# CH32V205V-R0.net
KiCad netlist of a schematic drawn in Altium Designer
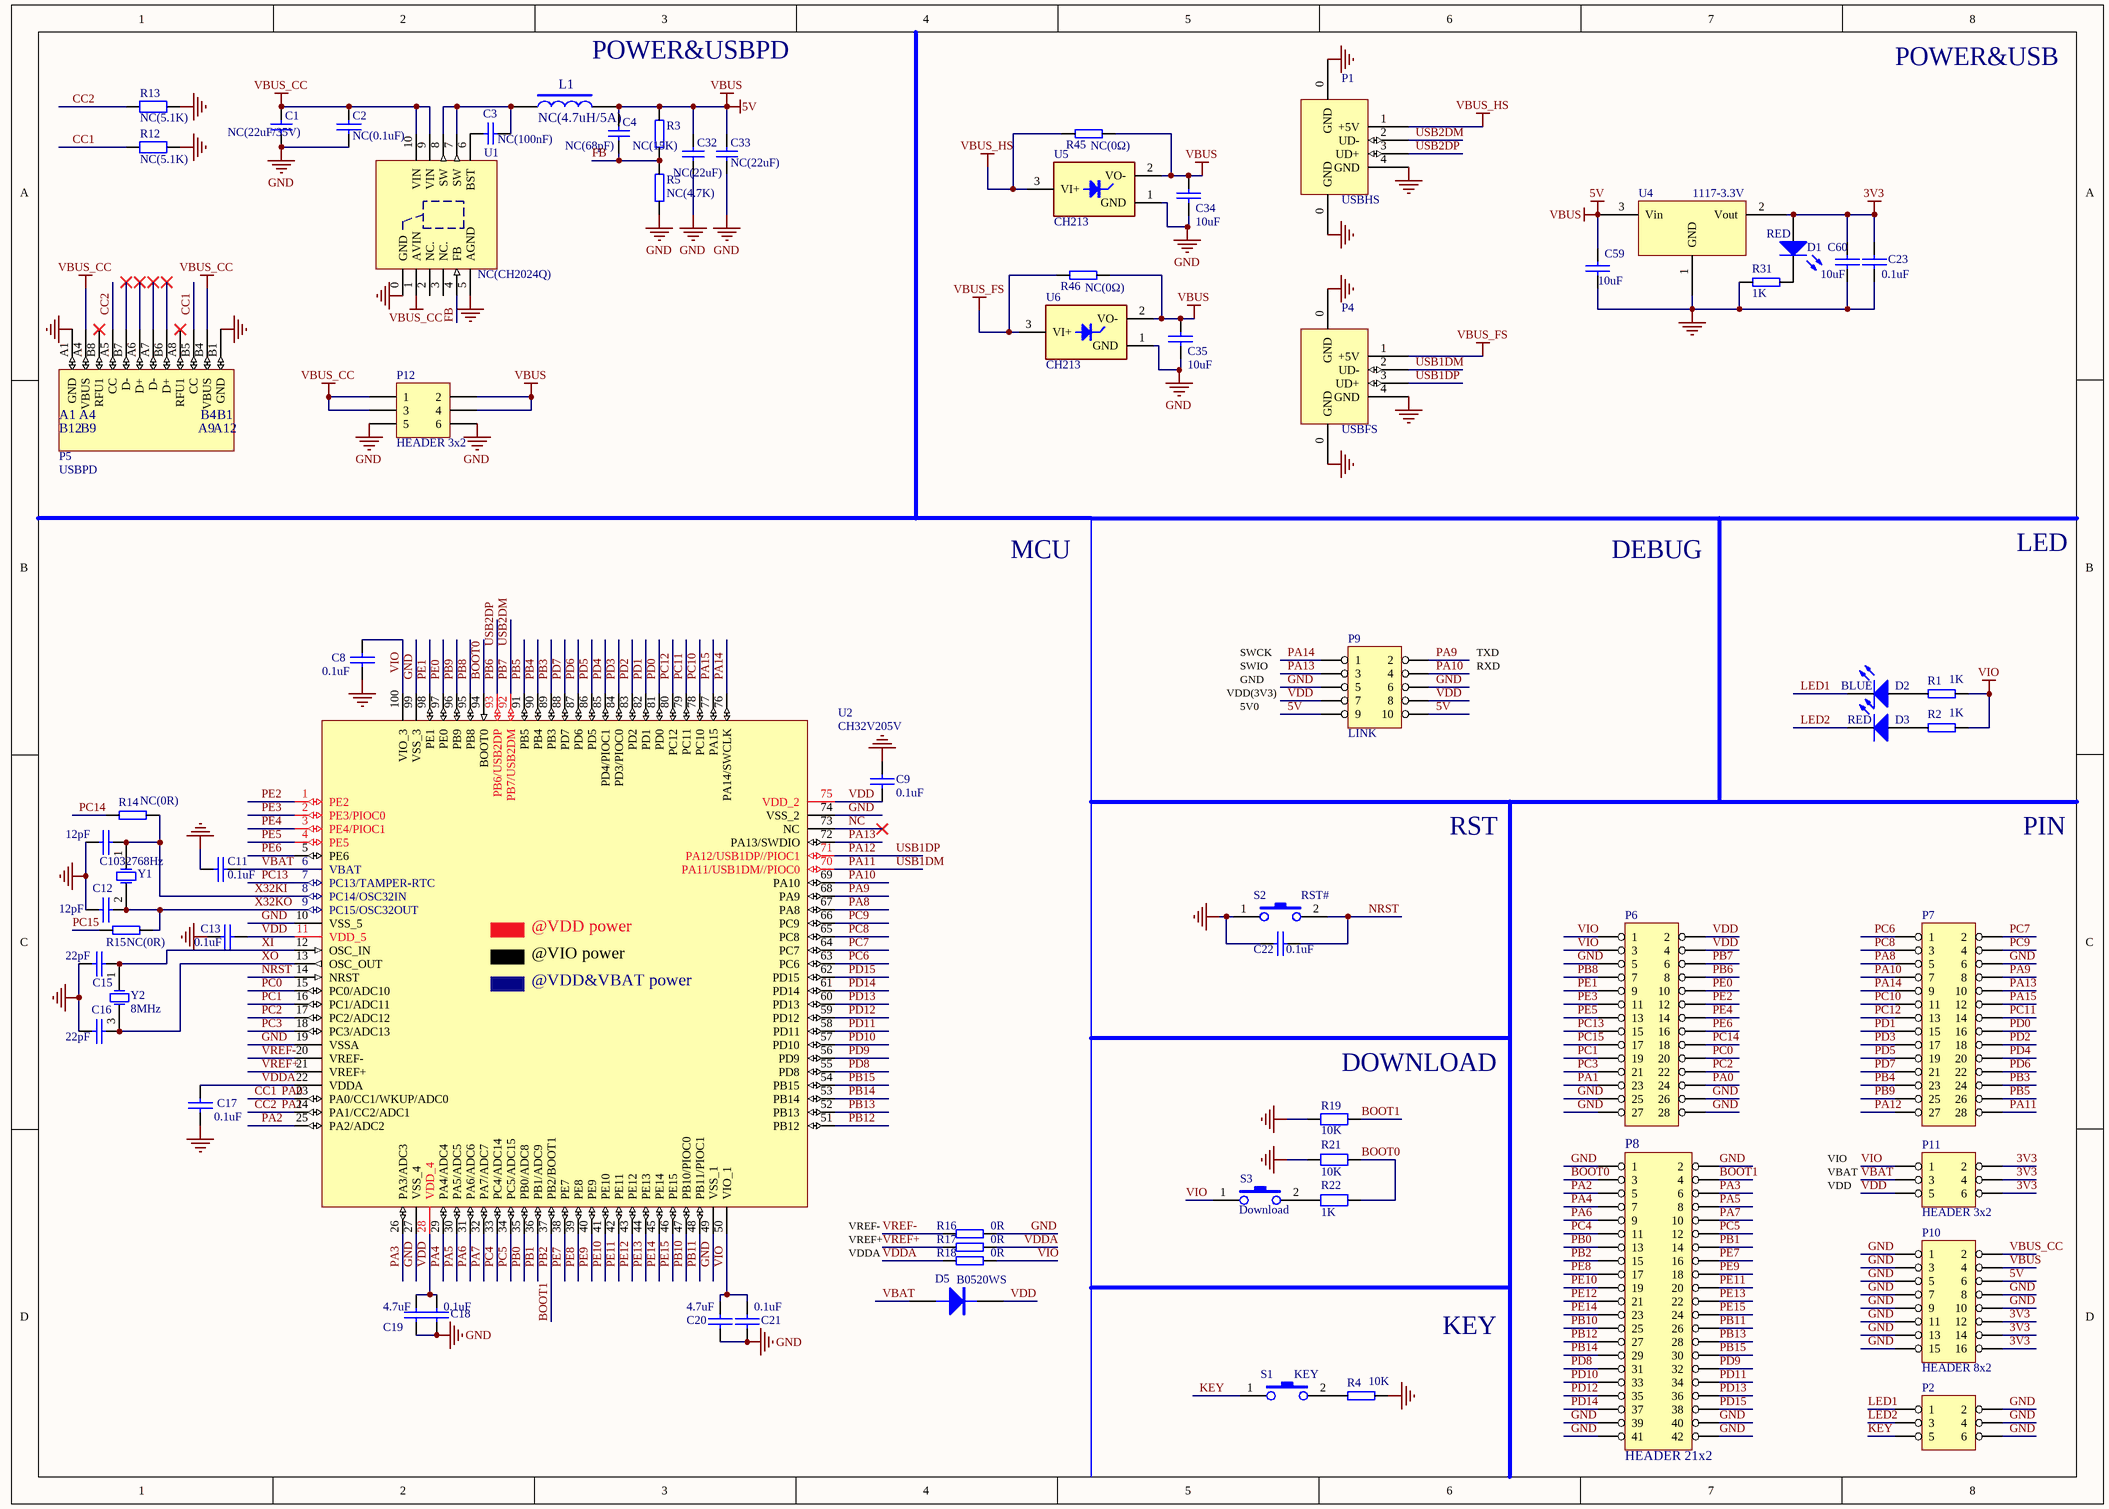
[diagram p0: CH32V205V-R0.SchDoc]

(export (version "E")
  (design (tool "Eeschema 10.0.6"))
  (components
    (comp (ref "C1")
      (value "NC(22uF/35V)")
      (footprint "0805_C")
      (description "贴片电容")
      (libsource (lib "Miscellaneous Devices LC") (part "0603 100nF (104) 10% 50V"))
    )
    (comp (ref "C2")
      (value "NC(0.1uF)")
      (footprint "0402_C")
      (description "Capacitor")
      (libsource (lib "*") (part "CAP"))
    )
    (comp (ref "C3")
      (value "NC(100nF)")
      (footprint "0402_C")
      (description "贴片电容")
      (libsource (lib "Miscellaneous Devices LC") (part "0603 1uF (105) 10% 50V"))
    )
    (comp (ref "C4")
      (value "NC(68pF)")
      (footprint "0402_C")
      (description "贴片电容")
      (libsource (lib "Miscellaneous Devices LC") (part "0603 100nF (104) 10% 50V"))
    )
    (comp (ref "C8")
      (value "0.1uF")
      (footprint "0402_C")
      (description "Capacitor")
      (libsource (lib "*") (part "CAP"))
    )
    (comp (ref "C9")
      (value "0.1uF")
      (footprint "0402_C")
      (description "Capacitor")
      (libsource (lib "*") (part "CAP"))
    )
    (comp (ref "C10")
      (value "12pF")
      (footprint "0402_C")
      (description "Capacitor")
      (libsource (lib "*") (part "CAP"))
    )
    (comp (ref "C11")
      (value "0.1uF")
      (footprint "0402_C")
      (description "Capacitor")
      (libsource (lib "*") (part "CAP"))
    )
    (comp (ref "C12")
      (value "12pF")
      (footprint "0402_C")
      (description "Capacitor")
      (libsource (lib "*") (part "CAP"))
    )
    (comp (ref "C13")
      (value "0.1uF")
      (footprint "0402_C")
      (description "Capacitor")
      (libsource (lib "*") (part "CAP"))
    )
    (comp (ref "C15")
      (value "22pF")
      (footprint "0402_C")
      (description "Capacitor")
      (libsource (lib "*") (part "CAP"))
    )
    (comp (ref "C16")
      (value "22pF")
      (footprint "0402_C")
      (description "Capacitor")
      (libsource (lib "*") (part "CAP"))
    )
    (comp (ref "C17")
      (value "0.1uF")
      (footprint "0402_C")
      (description "Capacitor")
      (libsource (lib "*") (part "CAP"))
    )
    (comp (ref "C18")
      (value "0.1uF")
      (footprint "0402_C")
      (description "Capacitor")
      (libsource (lib "*") (part "CAP"))
    )
    (comp (ref "C19")
      (value "4.7uF")
      (footprint "0402_C")
      (description "Capacitor")
      (libsource (lib "*") (part "CAP"))
    )
    (comp (ref "C20")
      (value "4.7uF")
      (footprint "0402_C")
      (description "Capacitor")
      (libsource (lib "*") (part "CAP"))
    )
    (comp (ref "C21")
      (value "0.1uF")
      (footprint "0402_C")
      (description "Capacitor")
      (libsource (lib "*") (part "CAP"))
    )
    (comp (ref "C22")
      (value "0.1uF")
      (footprint "0402_C")
      (description "Capacitor")
      (libsource (lib "") (part "CAP_1"))
    )
    (comp (ref "C23")
      (value "0.1uF")
      (footprint "0402_C")
      (description "Capacitor")
      (libsource (lib "*") (part "CAP"))
    )
    (comp (ref "C32")
      (value "NC(22uF)")
      (footprint "0805_C")
      (description "贴片电容")
      (libsource (lib "Miscellaneous Devices LC") (part "0603 100nF (104) 10% 50V"))
    )
    (comp (ref "C33")
      (value "NC(22uF)")
      (footprint "0805_C")
      (description "贴片电容")
      (libsource (lib "Miscellaneous Devices LC") (part "0603 100nF (104) 10% 50V"))
    )
    (comp (ref "C34")
      (value "10uF")
      (footprint "0603_C")
      (description "Capacitor")
      (libsource (lib "") (part "CAP_1"))
    )
    (comp (ref "C35")
      (value "10uF")
      (footprint "0603_C")
      (description "Capacitor")
      (libsource (lib "") (part "CAP_1"))
    )
    (comp (ref "C59")
      (value "10uF")
      (footprint "0603_C")
      (description "Capacitor")
      (libsource (lib "*") (part "CAP"))
    )
    (comp (ref "C60")
      (value "10uF")
      (footprint "0603_C")
      (description "Capacitor")
      (libsource (lib "*") (part "CAP"))
    )
    (comp (ref "D1")
      (value "RED")
      (footprint "0603+")
      (description "Typical INFRARED GaAs LED")
      (fields (field (name "PUBLISHER") "Altium Limited"))
      (libsource (lib "*") (part "LED0"))
    )
    (comp (ref "D2")
      (value "BLUE")
      (footprint "0603+")
      (description "Typical INFRARED GaAs LED")
      (fields (field (name "PUBLISHER") "Altium Limited"))
      (libsource (lib "*") (part "LED0"))
    )
    (comp (ref "D3")
      (value "RED")
      (footprint "0603+")
      (description "Typical INFRARED GaAs LED")
      (fields (field (name "PUBLISHER") "Altium Limited"))
      (libsource (lib "*") (part "LED0"))
    )
    (comp (ref "D5")
      (value "B0520WS")
      (footprint "SOD-323")
      (description "Diode")
      (libsource (lib "*") (part "DIODE"))
    )
    (comp (ref "L1")
      (value "NC(4.7uH/5A)")
      (footprint "IND-SMD_L7.0-W6.6")
      (libsource (lib "wch_sch_others") (part "INDUCTOR"))
    )
    (comp (ref "P1")
      (value "USBHS")
      (footprint "USBAF")
      (description "USB Port")
      (libsource (lib "*") (part "USB"))
    )
    (comp (ref "P2")
      (value "IO")
      (footprint "MYPCB:IDC6-2.54mm")
      (description "Header, 3-Pin, Dual row")
      (libsource (lib "wch_sch_others") (part "HEADER 3x2"))
    )
    (comp (ref "P4")
      (value "USBFS")
      (footprint "USBAF")
      (description "USB Port")
      (libsource (lib "*") (part "USB"))
    )
    (comp (ref "P5")
      (value "USBPD")
      (footprint "TYPE-C-Receptacle-2.0")
      (libsource (lib "*") (part "TYPE-C1"))
    )
    (comp (ref "P6")
      (value "~")
      (footprint "MYPCB:IDC28-2.54MM")
      (description "Header, 14-Pin, Dual row")
      (libsource (lib "wch_sch_others") (part "HEADER 14x2"))
    )
    (comp (ref "P7")
      (value "~")
      (footprint "MYPCB:IDC28-2.54MM")
      (description "Header, 14-Pin, Dual row")
      (libsource (lib "wch_sch_others") (part "HEADER 14x2"))
    )
    (comp (ref "P8")
      (value "HEADER 21x2")
      (footprint "MYPCB:IDC42-2.54MM")
      (description "Header, 21-Pin, Dual row")
      (libsource (lib "wch_sch_others") (part "HEADER 21x2"))
    )
    (comp (ref "P9")
      (value "LINK")
      (footprint "MYPCB:IDC10-2.54mm")
      (description "Header, 5-Pin, Dual row")
      (libsource (lib "wch_sch_others") (part "HEADER 5x2"))
    )
    (comp (ref "P10")
      (value "HEADER 8x2")
      (footprint "MYPCB:IDC16-2.54mm")
      (description "Header, 8-Pin, Dual row")
      (libsource (lib "wch_sch_others") (part "HEADER 8x2"))
    )
    (comp (ref "P11")
      (value "HEADER 3x2")
      (footprint "MYPCB:IDC6-2.54mm")
      (description "Header, 3-Pin, Dual row")
      (libsource (lib "wch_sch_others") (part "HEADER 3x2"))
    )
    (comp (ref "P12")
      (value "HEADER 3x2")
      (footprint "MYPCB:IDC6-2.54mm")
      (description "Header, 3-Pin, Dual row")
      (libsource (lib "") (part "HEADER 3x2_1"))
    )
    (comp (ref "R1") (value "1K") (footprint "0402") (libsource (lib "wch_sch_others") (part "RES")))
    (comp (ref "R2") (value "1K") (footprint "0402") (libsource (lib "wch_sch_others") (part "RES")))
    (comp (ref "R3") (value "NC(15K)") (footprint "0402") (libsource (lib "wch_sch_others(1)") (part "RES")))
    (comp (ref "R4") (value "10K") (footprint "0402") (libsource (lib "wch_sch_others") (part "RES")))
    (comp (ref "R5") (value "NC(4.7K)") (footprint "0402") (libsource (lib "wch_sch_others(1)") (part "RES")))
    (comp (ref "R12")
      (value "NC(5.1K)")
      (footprint "0402")
      (description "Resistor")
      (libsource (lib "") (part "Res2_1"))
    )
    (comp (ref "R13")
      (value "NC(5.1K)")
      (footprint "0402")
      (description "Resistor")
      (libsource (lib "") (part "Res2_1"))
    )
    (comp (ref "R14") (value "NC(0R)") (footprint "0402") (libsource (lib "wch_sch_others") (part "RES")))
    (comp (ref "R15") (value "NC(0R)") (footprint "0402") (libsource (lib "wch_sch_others") (part "RES")))
    (comp (ref "R16") (value "0R") (footprint "0402") (libsource (lib "*") (part "R")))
    (comp (ref "R17") (value "0R") (footprint "0402") (libsource (lib "*") (part "R")))
    (comp (ref "R18") (value "0R") (footprint "0402") (libsource (lib "*") (part "R")))
    (comp (ref "R19")
      (value "10K")
      (footprint "0402")
      (description "Resistor")
      (fields (field (name "PUBLISHER") "Altium Limited"))
      (libsource (lib "Miscellaneous Devices") (part "Res2"))
    )
    (comp (ref "R21")
      (value "10K")
      (footprint "0402")
      (description "Resistor")
      (fields (field (name "PUBLISHER") "Altium Limited"))
      (libsource (lib "Miscellaneous Devices") (part "Res2"))
    )
    (comp (ref "R22")
      (value "1K")
      (footprint "0402")
      (description "Resistor")
      (fields (field (name "PUBLISHER") "Altium Limited"))
      (libsource (lib "Miscellaneous Devices") (part "Res2"))
    )
    (comp (ref "R31") (value "1K") (footprint "0402") (libsource (lib "wch_sch_others") (part "RES")))
    (comp (ref "R45") (value "NC(0Ω)") (footprint "0402") (libsource (lib "wch_sch_others") (part "RES")))
    (comp (ref "R46") (value "NC(0Ω)") (footprint "0402") (libsource (lib "wch_sch_others") (part "RES")))
    (comp (ref "S1")
      (value "KEY")
      (footprint "SMD_6.1x3.65x2.5mm-KEY")
      (libsource (lib "wch_sch_others") (part "KEY1"))
    )
    (comp (ref "S2")
      (value "RST#")
      (footprint "SMD_6.1x3.65x2.5mm-KEY")
      (libsource (lib "wch_sch_others") (part "KEY1"))
    )
    (comp (ref "S3")
      (value "Download")
      (footprint "SMD_6.1x3.65x2.5mm-KEY")
      (libsource (lib "wch_sch_others") (part "KEY1"))
    )
    (comp (ref "U1")
      (value "NC(CH2024Q)")
      (footprint "DFN10_3X3")
      (description "Step-Down DC-DC Converter, 28V input, FB 1.2V, 3A output")
      (libsource (lib "DHXXXSCH") (part "CH2024Q"))
    )
    (comp (ref "U2")
      (value "CH32V205V")
      (footprint "LQFP100")
      (description "RISC-V MCU, 192MHz, USB_480M, USB FS, PD, PIOC, ADC, TKEY, 2*OPA, 2*CMP")
      (libsource (lib "CHXXX") (part "CH32V205V"))
    )
    (comp (ref "U4")
      (value "1117-3.3V")
      (footprint "SOT-223")
      (libsource (lib "wch_sch_others") (part "1117-3.3V"))
    )
    (comp (ref "U5")
      (value "CH213")
      (footprint "SOT-23-3")
      (description "Ideal Diode 5V*1A")
      (libsource (lib "CHXXX") (part "CH213E"))
    )
    (comp (ref "U6")
      (value "CH213")
      (footprint "SOT-23-3")
      (description "Ideal Diode 5V*1A")
      (libsource (lib "CHXXX") (part "CH213E"))
    )
    (comp (ref "Y1")
      (value "32768Hz")
      (footprint "FC-135")
      (description "Crystal Oscillator")
      (fields (field (name "PUBLISHER") "Altium Limited"))
      (libsource (lib "") (part "XTAL_1"))
    )
    (comp (ref "Y2")
      (value "8MHz")
      (footprint "XT3225")
      (description "Crystal Oscillator")
      (fields (field (name "PUBLISHER") "Altium Limited"))
      (libsource (lib "*") (part "XTAL"))
    )
  )
  (nets
    (net (code "2") (name "/BOOT0") (class "Default")
      (node (ref "P8") (pin "3") (pinfunction "3_3") (pintype "passive"))
      (node (ref "R21") (pin "1") (pinfunction "1_1") (pintype "passive"))
      (node (ref "R22") (pin "1") (pinfunction "1_1") (pintype "passive"))
      (node (ref "U2") (pin "94") (pinfunction "BOOT0_94") (pintype "input"))
    )
    (net (code "3") (name "/BOOT1") (class "Default")
      (node (ref "P8") (pin "15") (pinfunction "15_15") (pintype "passive"))
      (node (ref "P8") (pin "4") (pinfunction "4_4") (pintype "passive"))
      (node (ref "R19") (pin "1") (pinfunction "1_1") (pintype "passive"))
      (node (ref "U2") (pin "37") (pinfunction "PB2/BOOT1_37") (pintype "bidirectional"))
    )
    (net (code "4") (name "/CC1") (class "Default")
      (node (ref "P5") (pin "B5") (pinfunction "CC_B5") (pintype "bidirectional"))
      (node (ref "P6") (pin "24") (pinfunction "24_24") (pintype "passive"))
      (node (ref "R12") (pin "1") (pinfunction "1_1") (pintype "passive"))
      (node (ref "U2") (pin "23") (pinfunction "PA0/CC1/WKUP/ADC0_23") (pintype "bidirectional"))
    )
    (net (code "5") (name "/CC2") (class "Default")
      (node (ref "P5") (pin "A5") (pinfunction "CC_A5") (pintype "bidirectional"))
      (node (ref "P6") (pin "23") (pinfunction "23_23") (pintype "passive"))
      (node (ref "R13") (pin "1") (pinfunction "1_1") (pintype "passive"))
      (node (ref "U2") (pin "24") (pinfunction "PA1/CC2/ADC1_24") (pintype "bidirectional"))
    )
    (net (code "6") (name "/FB") (class "Default")
      (node (ref "C4") (pin "2") (pinfunction "2_2") (pintype "passive"))
      (node (ref "R3") (pin "1") (pintype "passive"))
      (node (ref "R5") (pin "2") (pintype "passive"))
      (node (ref "U1") (pin "4") (pinfunction "FB_4") (pintype "input"))
    )
    (net (code "7") (name "/KEY") (class "Default")
      (node (ref "P2") (pin "5") (pinfunction "5_5") (pintype "passive"))
      (node (ref "S1") (pin "1") (pinfunction "1_1") (pintype "passive"))
    )
    (net (code "8") (name "/LED1") (class "Default")
      (node (ref "D2") (pin "2") (pinfunction "K_2") (pintype "passive"))
      (node (ref "P2") (pin "1") (pinfunction "1_1") (pintype "passive"))
    )
    (net (code "9") (name "/LED2") (class "Default")
      (node (ref "D3") (pin "2") (pinfunction "K_2") (pintype "passive"))
      (node (ref "P2") (pin "3") (pinfunction "3_3") (pintype "passive"))
    )
    (net (code "10") (name "/NC") (class "Default")
      (node (ref "U2") (pin "73") (pinfunction "NC_73") (pintype "tri_state+no_connect"))
    )
    (net (code "11") (name "/NRST") (class "Default")
      (node (ref "C22") (pin "2") (pinfunction "2_2") (pintype "passive"))
      (node (ref "S2") (pin "2") (pinfunction "2_2") (pintype "passive"))
      (node (ref "U2") (pin "14") (pinfunction "NRST_14") (pintype "input"))
    )
    (net (code "12") (name "/PA2") (class "Default")
      (node (ref "P8") (pin "5") (pinfunction "5_5") (pintype "passive"))
      (node (ref "U2") (pin "25") (pinfunction "PA2/ADC2_25") (pintype "bidirectional"))
    )
    (net (code "13") (name "/PA3") (class "Default")
      (node (ref "P8") (pin "6") (pinfunction "6_6") (pintype "passive"))
      (node (ref "U2") (pin "26") (pinfunction "PA3/ADC3_26") (pintype "bidirectional"))
    )
    (net (code "14") (name "/PA4") (class "Default")
      (node (ref "P8") (pin "7") (pinfunction "7_7") (pintype "passive"))
      (node (ref "U2") (pin "29") (pinfunction "PA4/ADC4_29") (pintype "bidirectional"))
    )
    (net (code "15") (name "/PA5") (class "Default")
      (node (ref "P8") (pin "8") (pinfunction "8_8") (pintype "passive"))
      (node (ref "U2") (pin "30") (pinfunction "PA5/ADC5_30") (pintype "bidirectional"))
    )
    (net (code "16") (name "/PA6") (class "Default")
      (node (ref "P8") (pin "9") (pinfunction "9_9") (pintype "passive"))
      (node (ref "U2") (pin "31") (pinfunction "PA6/ADC6_31") (pintype "bidirectional"))
    )
    (net (code "17") (name "/PA7") (class "Default")
      (node (ref "P8") (pin "10") (pinfunction "10_10") (pintype "passive"))
      (node (ref "U2") (pin "32") (pinfunction "PA7/ADC7_32") (pintype "bidirectional"))
    )
    (net (code "18") (name "/PA8") (class "Default")
      (node (ref "P7") (pin "5") (pinfunction "5_5") (pintype "passive"))
      (node (ref "U2") (pin "67") (pinfunction "PA8_67") (pintype "bidirectional"))
    )
    (net (code "19") (name "/PA9") (class "Default")
      (node (ref "P7") (pin "8") (pinfunction "8_8") (pintype "passive"))
      (node (ref "P9") (pin "2") (pinfunction "2_2") (pintype "passive"))
      (node (ref "U2") (pin "68") (pinfunction "PA9_68") (pintype "bidirectional"))
    )
    (net (code "20") (name "/PA10") (class "Default")
      (node (ref "P7") (pin "7") (pinfunction "7_7") (pintype "passive"))
      (node (ref "P9") (pin "4") (pinfunction "4_4") (pintype "passive"))
      (node (ref "U2") (pin "69") (pinfunction "PA10_69") (pintype "bidirectional"))
    )
    (net (code "21") (name "/PA11") (class "Default")
      (node (ref "P4") (pin "2") (pinfunction "UD-_2") (pintype "bidirectional"))
      (node (ref "P7") (pin "28") (pinfunction "28_28") (pintype "passive"))
      (node (ref "U2") (pin "70") (pinfunction "PA11/USB1DM//PIOC0_70") (pintype "bidirectional"))
    )
    (net (code "22") (name "/PA12") (class "Default")
      (node (ref "P4") (pin "3") (pinfunction "UD+_3") (pintype "bidirectional"))
      (node (ref "P7") (pin "27") (pinfunction "27_27") (pintype "passive"))
      (node (ref "U2") (pin "71") (pinfunction "PA12/USB1DP//PIOC1_71") (pintype "bidirectional"))
    )
    (net (code "23") (name "/PA13") (class "Default")
      (node (ref "P7") (pin "10") (pinfunction "10_10") (pintype "passive"))
      (node (ref "P9") (pin "3") (pinfunction "3_3") (pintype "passive"))
      (node (ref "U2") (pin "72") (pinfunction "PA13/SWDIO_72") (pintype "bidirectional"))
    )
    (net (code "24") (name "/PA14") (class "Default")
      (node (ref "P7") (pin "9") (pinfunction "9_9") (pintype "passive"))
      (node (ref "P9") (pin "1") (pinfunction "1_1") (pintype "passive"))
      (node (ref "U2") (pin "76") (pinfunction "PA14/SWCLK_76") (pintype "bidirectional"))
    )
    (net (code "25") (name "/PA15") (class "Default")
      (node (ref "P7") (pin "12") (pinfunction "12_12") (pintype "passive"))
      (node (ref "U2") (pin "77") (pinfunction "PA15_77") (pintype "bidirectional"))
    )
    (net (code "26") (name "/PB0") (class "Default")
      (node (ref "P8") (pin "13") (pinfunction "13_13") (pintype "passive"))
      (node (ref "U2") (pin "35") (pinfunction "PB0/ADC8_35") (pintype "bidirectional"))
    )
    (net (code "27") (name "/PB1") (class "Default")
      (node (ref "P8") (pin "14") (pinfunction "14_14") (pintype "passive"))
      (node (ref "U2") (pin "36") (pinfunction "PB1/ADC9_36") (pintype "bidirectional"))
    )
    (net (code "28") (name "/PB3") (class "Default")
      (node (ref "P7") (pin "24") (pinfunction "24_24") (pintype "passive"))
      (node (ref "U2") (pin "89") (pinfunction "PB3_89") (pintype "bidirectional"))
    )
    (net (code "29") (name "/PB4") (class "Default")
      (node (ref "P7") (pin "23") (pinfunction "23_23") (pintype "passive"))
      (node (ref "U2") (pin "90") (pinfunction "PB4_90") (pintype "bidirectional"))
    )
    (net (code "30") (name "/PB5") (class "Default")
      (node (ref "P7") (pin "26") (pinfunction "26_26") (pintype "passive"))
      (node (ref "U2") (pin "91") (pinfunction "PB5_91") (pintype "bidirectional"))
    )
    (net (code "31") (name "/PB6") (class "Default")
      (node (ref "P1") (pin "3") (pinfunction "UD+_3") (pintype "bidirectional"))
      (node (ref "P6") (pin "8") (pinfunction "8_8") (pintype "passive"))
      (node (ref "U2") (pin "93") (pinfunction "PB6/USB2DP_93") (pintype "bidirectional"))
    )
    (net (code "32") (name "/PB7") (class "Default")
      (node (ref "P1") (pin "2") (pinfunction "UD-_2") (pintype "bidirectional"))
      (node (ref "P6") (pin "6") (pinfunction "6_6") (pintype "passive"))
      (node (ref "U2") (pin "92") (pinfunction "PB7/USB2DM_92") (pintype "bidirectional"))
    )
    (net (code "33") (name "/PB8") (class "Default")
      (node (ref "P6") (pin "7") (pinfunction "7_7") (pintype "passive"))
      (node (ref "U2") (pin "95") (pinfunction "PB8_95") (pintype "bidirectional"))
    )
    (net (code "34") (name "/PB9") (class "Default")
      (node (ref "P7") (pin "25") (pinfunction "25_25") (pintype "passive"))
      (node (ref "U2") (pin "96") (pinfunction "PB9_96") (pintype "bidirectional"))
    )
    (net (code "35") (name "/PB10") (class "Default")
      (node (ref "P8") (pin "25") (pinfunction "25_25") (pintype "passive"))
      (node (ref "U2") (pin "47") (pinfunction "PB10/PIOC0_47") (pintype "bidirectional"))
    )
    (net (code "36") (name "/PB11") (class "Default")
      (node (ref "P8") (pin "26") (pinfunction "26_26") (pintype "passive"))
      (node (ref "U2") (pin "48") (pinfunction "PB11/PIOC1_48") (pintype "bidirectional"))
    )
    (net (code "37") (name "/PB12") (class "Default")
      (node (ref "P8") (pin "27") (pinfunction "27_27") (pintype "passive"))
      (node (ref "U2") (pin "51") (pinfunction "PB12_51") (pintype "bidirectional"))
    )
    (net (code "38") (name "/PB13") (class "Default")
      (node (ref "P8") (pin "28") (pinfunction "28_28") (pintype "passive"))
      (node (ref "U2") (pin "52") (pinfunction "PB13_52") (pintype "bidirectional"))
    )
    (net (code "39") (name "/PB14") (class "Default")
      (node (ref "P8") (pin "29") (pinfunction "29_29") (pintype "passive"))
      (node (ref "U2") (pin "53") (pinfunction "PB14_53") (pintype "bidirectional"))
    )
    (net (code "40") (name "/PB15") (class "Default")
      (node (ref "P8") (pin "30") (pinfunction "30_30") (pintype "passive"))
      (node (ref "U2") (pin "54") (pinfunction "PB15_54") (pintype "bidirectional"))
    )
    (net (code "41") (name "/PC0") (class "Default")
      (node (ref "P6") (pin "20") (pinfunction "20_20") (pintype "passive"))
      (node (ref "U2") (pin "15") (pinfunction "PC0/ADC10_15") (pintype "bidirectional"))
    )
    (net (code "42") (name "/PC1") (class "Default")
      (node (ref "P6") (pin "19") (pinfunction "19_19") (pintype "passive"))
      (node (ref "U2") (pin "16") (pinfunction "PC1/ADC11_16") (pintype "bidirectional"))
    )
    (net (code "43") (name "/PC2") (class "Default")
      (node (ref "P6") (pin "22") (pinfunction "22_22") (pintype "passive"))
      (node (ref "U2") (pin "17") (pinfunction "PC2/ADC12_17") (pintype "bidirectional"))
    )
    (net (code "44") (name "/PC3") (class "Default")
      (node (ref "P6") (pin "21") (pinfunction "21_21") (pintype "passive"))
      (node (ref "U2") (pin "18") (pinfunction "PC3/ADC13_18") (pintype "bidirectional"))
    )
    (net (code "45") (name "/PC4") (class "Default")
      (node (ref "P8") (pin "11") (pinfunction "11_11") (pintype "passive"))
      (node (ref "U2") (pin "33") (pinfunction "PC4/ADC14_33") (pintype "bidirectional"))
    )
    (net (code "46") (name "/PC5") (class "Default")
      (node (ref "P8") (pin "12") (pinfunction "12_12") (pintype "passive"))
      (node (ref "U2") (pin "34") (pinfunction "PC5/ADC15_34") (pintype "bidirectional"))
    )
    (net (code "47") (name "/PC6") (class "Default")
      (node (ref "P7") (pin "1") (pinfunction "1_1") (pintype "passive"))
      (node (ref "U2") (pin "63") (pinfunction "PC6_63") (pintype "bidirectional"))
    )
    (net (code "48") (name "/PC7") (class "Default")
      (node (ref "P7") (pin "2") (pinfunction "2_2") (pintype "passive"))
      (node (ref "U2") (pin "64") (pinfunction "PC7_64") (pintype "bidirectional"))
    )
    (net (code "49") (name "/PC8") (class "Default")
      (node (ref "P7") (pin "3") (pinfunction "3_3") (pintype "passive"))
      (node (ref "U2") (pin "65") (pinfunction "PC8_65") (pintype "bidirectional"))
    )
    (net (code "50") (name "/PC9") (class "Default")
      (node (ref "P7") (pin "4") (pinfunction "4_4") (pintype "passive"))
      (node (ref "U2") (pin "66") (pinfunction "PC9_66") (pintype "bidirectional"))
    )
    (net (code "51") (name "/PC10") (class "Default")
      (node (ref "P7") (pin "11") (pinfunction "11_11") (pintype "passive"))
      (node (ref "U2") (pin "78") (pinfunction "PC10_78") (pintype "bidirectional"))
    )
    (net (code "52") (name "/PC11") (class "Default")
      (node (ref "P7") (pin "14") (pinfunction "14_14") (pintype "passive"))
      (node (ref "U2") (pin "79") (pinfunction "PC11_79") (pintype "bidirectional"))
    )
    (net (code "53") (name "/PC12") (class "Default")
      (node (ref "P7") (pin "13") (pinfunction "13_13") (pintype "passive"))
      (node (ref "U2") (pin "80") (pinfunction "PC12_80") (pintype "bidirectional"))
    )
    (net (code "54") (name "/PC13") (class "Default")
      (node (ref "P6") (pin "15") (pinfunction "15_15") (pintype "passive"))
      (node (ref "U2") (pin "7") (pinfunction "PC13/TAMPER-RTC_7") (pintype "bidirectional"))
    )
    (net (code "55") (name "/PC14") (class "Default")
      (node (ref "P6") (pin "18") (pinfunction "18_18") (pintype "passive"))
      (node (ref "R14") (pin "1") (pintype "passive"))
    )
    (net (code "56") (name "/PC15") (class "Default")
      (node (ref "P6") (pin "17") (pinfunction "17_17") (pintype "passive"))
      (node (ref "R15") (pin "1") (pintype "passive"))
    )
    (net (code "57") (name "/PD0") (class "Default")
      (node (ref "P7") (pin "16") (pinfunction "16_16") (pintype "passive"))
      (node (ref "U2") (pin "81") (pinfunction "PD0_81") (pintype "bidirectional"))
    )
    (net (code "58") (name "/PD1") (class "Default")
      (node (ref "P7") (pin "15") (pinfunction "15_15") (pintype "passive"))
      (node (ref "U2") (pin "82") (pinfunction "PD1_82") (pintype "bidirectional"))
    )
    (net (code "59") (name "/PD2") (class "Default")
      (node (ref "P7") (pin "18") (pinfunction "18_18") (pintype "passive"))
      (node (ref "U2") (pin "83") (pinfunction "PD2_83") (pintype "bidirectional"))
    )
    (net (code "60") (name "/PD3") (class "Default")
      (node (ref "P7") (pin "17") (pinfunction "17_17") (pintype "passive"))
      (node (ref "U2") (pin "84") (pinfunction "PD3/PIOC0_84") (pintype "bidirectional"))
    )
    (net (code "61") (name "/PD4") (class "Default")
      (node (ref "P7") (pin "20") (pinfunction "20_20") (pintype "passive"))
      (node (ref "U2") (pin "85") (pinfunction "PD4/PIOC1_85") (pintype "bidirectional"))
    )
    (net (code "62") (name "/PD5") (class "Default")
      (node (ref "P7") (pin "19") (pinfunction "19_19") (pintype "passive"))
      (node (ref "U2") (pin "86") (pinfunction "PD5_86") (pintype "bidirectional"))
    )
    (net (code "63") (name "/PD6") (class "Default")
      (node (ref "P7") (pin "22") (pinfunction "22_22") (pintype "passive"))
      (node (ref "U2") (pin "87") (pinfunction "PD6_87") (pintype "bidirectional"))
    )
    (net (code "64") (name "/PD7") (class "Default")
      (node (ref "P7") (pin "21") (pinfunction "21_21") (pintype "passive"))
      (node (ref "U2") (pin "88") (pinfunction "PD7_88") (pintype "bidirectional"))
    )
    (net (code "65") (name "/PD8") (class "Default")
      (node (ref "P8") (pin "31") (pinfunction "31_31") (pintype "passive"))
      (node (ref "U2") (pin "55") (pinfunction "PD8_55") (pintype "bidirectional"))
    )
    (net (code "66") (name "/PD9") (class "Default")
      (node (ref "P8") (pin "32") (pinfunction "32_32") (pintype "passive"))
      (node (ref "U2") (pin "56") (pinfunction "PD9_56") (pintype "bidirectional"))
    )
    (net (code "67") (name "/PD10") (class "Default")
      (node (ref "P8") (pin "33") (pinfunction "33_33") (pintype "passive"))
      (node (ref "U2") (pin "57") (pinfunction "PD10_57") (pintype "bidirectional"))
    )
    (net (code "68") (name "/PD11") (class "Default")
      (node (ref "P8") (pin "34") (pinfunction "34_34") (pintype "passive"))
      (node (ref "U2") (pin "58") (pinfunction "PD11_58") (pintype "bidirectional"))
    )
    (net (code "69") (name "/PD12") (class "Default")
      (node (ref "P8") (pin "35") (pinfunction "35_35") (pintype "passive"))
      (node (ref "U2") (pin "59") (pinfunction "PD12_59") (pintype "bidirectional"))
    )
    (net (code "70") (name "/PD13") (class "Default")
      (node (ref "P8") (pin "36") (pinfunction "36_36") (pintype "passive"))
      (node (ref "U2") (pin "60") (pinfunction "PD13_60") (pintype "bidirectional"))
    )
    (net (code "71") (name "/PD14") (class "Default")
      (node (ref "P8") (pin "37") (pinfunction "37_37") (pintype "passive"))
      (node (ref "U2") (pin "61") (pinfunction "PD14_61") (pintype "bidirectional"))
    )
    (net (code "72") (name "/PD15") (class "Default")
      (node (ref "P8") (pin "38") (pinfunction "38_38") (pintype "passive"))
      (node (ref "U2") (pin "62") (pinfunction "PD15_62") (pintype "bidirectional"))
    )
    (net (code "73") (name "/PE0") (class "Default")
      (node (ref "P6") (pin "10") (pinfunction "10_10") (pintype "passive"))
      (node (ref "U2") (pin "97") (pinfunction "PE0_97") (pintype "bidirectional"))
    )
    (net (code "74") (name "/PE1") (class "Default")
      (node (ref "P6") (pin "9") (pinfunction "9_9") (pintype "passive"))
      (node (ref "U2") (pin "98") (pinfunction "PE1_98") (pintype "bidirectional"))
    )
    (net (code "75") (name "/PE2") (class "Default")
      (node (ref "P6") (pin "12") (pinfunction "12_12") (pintype "passive"))
      (node (ref "U2") (pin "1") (pinfunction "PE2_1") (pintype "bidirectional"))
    )
    (net (code "76") (name "/PE3") (class "Default")
      (node (ref "P6") (pin "11") (pinfunction "11_11") (pintype "passive"))
      (node (ref "U2") (pin "2") (pinfunction "PE3/PIOC0_2") (pintype "bidirectional"))
    )
    (net (code "77") (name "/PE4") (class "Default")
      (node (ref "P6") (pin "14") (pinfunction "14_14") (pintype "passive"))
      (node (ref "U2") (pin "3") (pinfunction "PE4/PIOC1_3") (pintype "bidirectional"))
    )
    (net (code "78") (name "/PE5") (class "Default")
      (node (ref "P6") (pin "13") (pinfunction "13_13") (pintype "passive"))
      (node (ref "U2") (pin "4") (pinfunction "PE5_4") (pintype "bidirectional"))
    )
    (net (code "79") (name "/PE6") (class "Default")
      (node (ref "P6") (pin "16") (pinfunction "16_16") (pintype "passive"))
      (node (ref "U2") (pin "5") (pinfunction "PE6_5") (pintype "bidirectional"))
    )
    (net (code "80") (name "/PE7") (class "Default")
      (node (ref "P8") (pin "16") (pinfunction "16_16") (pintype "passive"))
      (node (ref "U2") (pin "38") (pinfunction "PE7_38") (pintype "bidirectional"))
    )
    (net (code "81") (name "/PE8") (class "Default")
      (node (ref "P8") (pin "17") (pinfunction "17_17") (pintype "passive"))
      (node (ref "U2") (pin "39") (pinfunction "PE8_39") (pintype "bidirectional"))
    )
    (net (code "82") (name "/PE9") (class "Default")
      (node (ref "P8") (pin "18") (pinfunction "18_18") (pintype "passive"))
      (node (ref "U2") (pin "40") (pinfunction "PE9_40") (pintype "bidirectional"))
    )
    (net (code "83") (name "/PE10") (class "Default")
      (node (ref "P8") (pin "19") (pinfunction "19_19") (pintype "passive"))
      (node (ref "U2") (pin "41") (pinfunction "PE10_41") (pintype "bidirectional"))
    )
    (net (code "84") (name "/PE11") (class "Default")
      (node (ref "P8") (pin "20") (pinfunction "20_20") (pintype "passive"))
      (node (ref "U2") (pin "42") (pinfunction "PE11_42") (pintype "bidirectional"))
    )
    (net (code "85") (name "/PE12") (class "Default")
      (node (ref "P8") (pin "21") (pinfunction "21_21") (pintype "passive"))
      (node (ref "U2") (pin "43") (pinfunction "PE12_43") (pintype "bidirectional"))
    )
    (net (code "86") (name "/PE13") (class "Default")
      (node (ref "P8") (pin "22") (pinfunction "22_22") (pintype "passive"))
      (node (ref "U2") (pin "44") (pinfunction "PE13_44") (pintype "bidirectional"))
    )
    (net (code "87") (name "/PE14") (class "Default")
      (node (ref "P8") (pin "23") (pinfunction "23_23") (pintype "passive"))
      (node (ref "U2") (pin "45") (pinfunction "PE14_45") (pintype "bidirectional"))
    )
    (net (code "88") (name "/PE15") (class "Default")
      (node (ref "P8") (pin "24") (pinfunction "24_24") (pintype "passive"))
      (node (ref "U2") (pin "46") (pinfunction "PE15_46") (pintype "bidirectional"))
    )
    (net (code "89") (name "/VBAT") (class "Default")
      (node (ref "C11") (pin "2") (pinfunction "2_2") (pintype "passive"))
      (node (ref "D5") (pin "1") (pinfunction "A_1") (pintype "passive"))
      (node (ref "P11") (pin "3") (pinfunction "3_3") (pintype "passive"))
      (node (ref "U2") (pin "6") (pinfunction "VBAT_6") (pintype "power_in"))
    )
    (net (code "90") (name "/VDD") (class "Default")
      (node (ref "C13") (pin "1") (pinfunction "1_1") (pintype "passive"))
      (node (ref "C18") (pin "2") (pinfunction "2_2") (pintype "passive"))
      (node (ref "C19") (pin "1") (pinfunction "1_1") (pintype "passive"))
      (node (ref "C9") (pin "1") (pinfunction "1_1") (pintype "passive"))
      (node (ref "D5") (pin "2") (pinfunction "K_2") (pintype "passive"))
      (node (ref "P11") (pin "5") (pinfunction "5_5") (pintype "passive"))
      (node (ref "P6") (pin "2") (pinfunction "2_2") (pintype "passive"))
      (node (ref "P6") (pin "4") (pinfunction "4_4") (pintype "passive"))
      (node (ref "P9") (pin "7") (pinfunction "7_7") (pintype "passive"))
      (node (ref "P9") (pin "8") (pinfunction "8_8") (pintype "passive"))
      (node (ref "U2") (pin "11") (pinfunction "VDD_5_11") (pintype "power_in"))
      (node (ref "U2") (pin "28") (pinfunction "VDD_4_28") (pintype "power_in"))
      (node (ref "U2") (pin "75") (pinfunction "VDD_2_75") (pintype "power_in"))
    )
    (net (code "91") (name "/VDDA") (class "Default")
      (node (ref "C17") (pin "1") (pinfunction "1_1") (pintype "passive"))
      (node (ref "R17") (pin "1") (pinfunction "1_1") (pintype "passive"))
      (node (ref "R18") (pin "2") (pinfunction "2_2") (pintype "passive"))
      (node (ref "U2") (pin "22") (pinfunction "VDDA_22") (pintype "power_in"))
    )
    (net (code "92") (name "/VREF+") (class "Default")
      (node (ref "R17") (pin "2") (pinfunction "2_2") (pintype "passive"))
      (node (ref "U2") (pin "21") (pinfunction "VREF+_21") (pintype "power_in"))
    )
    (net (code "93") (name "/VREF-") (class "Default")
      (node (ref "R16") (pin "2") (pinfunction "2_2") (pintype "passive"))
      (node (ref "U2") (pin "20") (pinfunction "VREF-_20") (pintype "power_in"))
    )
    (net (code "94") (name "/X32KI") (class "Default")
      (node (ref "C10") (pin "2") (pinfunction "2_2") (pintype "passive"))
      (node (ref "R14") (pin "2") (pintype "passive"))
      (node (ref "U2") (pin "8") (pinfunction "PC14/OSC32IN_8") (pintype "bidirectional"))
      (node (ref "Y1") (pin "1") (pinfunction "OSC1_1") (pintype "passive"))
    )
    (net (code "95") (name "/X32KO") (class "Default")
      (node (ref "C12") (pin "2") (pinfunction "2_2") (pintype "passive"))
      (node (ref "R15") (pin "2") (pintype "passive"))
      (node (ref "U2") (pin "9") (pinfunction "PC15/OSC32OUT_9") (pintype "bidirectional"))
      (node (ref "Y1") (pin "2") (pinfunction "OSC2_2") (pintype "passive"))
    )
    (net (code "96") (name "/XI") (class "Default")
      (node (ref "C15") (pin "2") (pinfunction "2_2") (pintype "passive"))
      (node (ref "U2") (pin "12") (pinfunction "OSC_IN_12") (pintype "input"))
      (node (ref "Y2") (pin "1") (pinfunction "OSC1_1") (pintype "passive"))
    )
    (net (code "97") (name "/XO") (class "Default")
      (node (ref "C16") (pin "2") (pinfunction "2_2") (pintype "passive"))
      (node (ref "U2") (pin "13") (pinfunction "OSC_OUT_13") (pintype "output"))
      (node (ref "Y2") (pin "3") (pinfunction "OSC2_3") (pintype "passive"))
    )
    (net (code "98") (name "3V3") (class "Default")
      (node (ref "C23") (pin "1") (pinfunction "1_1") (pintype "passive"))
      (node (ref "C60") (pin "1") (pinfunction "1_1") (pintype "passive"))
      (node (ref "D1") (pin "1") (pinfunction "A_1") (pintype "passive"))
      (node (ref "P10") (pin "12") (pinfunction "12_12") (pintype "passive"))
      (node (ref "P10") (pin "14") (pinfunction "14_14") (pintype "passive"))
      (node (ref "P10") (pin "16") (pinfunction "16_16") (pintype "passive"))
      (node (ref "P11") (pin "2") (pinfunction "2_2") (pintype "passive"))
      (node (ref "P11") (pin "4") (pinfunction "4_4") (pintype "passive"))
      (node (ref "P11") (pin "6") (pinfunction "6_6") (pintype "passive"))
      (node (ref "U4") (pin "2") (pinfunction "Vout_2") (pintype "passive"))
    )
    (net (code "99") (name "5V") (class "Default")
      (node (ref "C32") (pin "2") (pinfunction "2_2") (pintype "passive"))
      (node (ref "C33") (pin "2") (pinfunction "2_2") (pintype "passive"))
      (node (ref "C34") (pin "1") (pinfunction "1_1") (pintype "passive"))
      (node (ref "C35") (pin "1") (pinfunction "1_1") (pintype "passive"))
      (node (ref "C4") (pin "1") (pinfunction "1_1") (pintype "passive"))
      (node (ref "C59") (pin "1") (pinfunction "1_1") (pintype "passive"))
      (node (ref "L1") (pin "2") (pinfunction "2_2") (pintype "passive"))
      (node (ref "P10") (pin "4") (pinfunction "4_4") (pintype "passive"))
      (node (ref "P10") (pin "6") (pinfunction "6_6") (pintype "passive"))
      (node (ref "P12") (pin "2") (pinfunction "2_2") (pintype "passive"))
      (node (ref "P12") (pin "4") (pinfunction "4_4") (pintype "passive"))
      (node (ref "P9") (pin "10") (pinfunction "10_10") (pintype "passive"))
      (node (ref "P9") (pin "9") (pinfunction "9_9") (pintype "passive"))
      (node (ref "R3") (pin "2") (pintype "passive"))
      (node (ref "R45") (pin "1") (pintype "passive"))
      (node (ref "R46") (pin "1") (pintype "passive"))
      (node (ref "U4") (pin "3") (pinfunction "Vin_3") (pintype "passive"))
      (node (ref "U5") (pin "2") (pinfunction "VO-_2") (pintype "power_in"))
      (node (ref "U6") (pin "2") (pinfunction "VO-_2") (pintype "power_in"))
    )
    (net (code "100") (name "GND") (class "Default")
      (node (ref "C1") (pin "1") (pinfunction "1_1") (pintype "passive"))
      (node (ref "C10") (pin "1") (pinfunction "1_1") (pintype "passive"))
      (node (ref "C11") (pin "1") (pinfunction "1_1") (pintype "passive"))
      (node (ref "C12") (pin "1") (pinfunction "1_1") (pintype "passive"))
      (node (ref "C13") (pin "2") (pinfunction "2_2") (pintype "passive"))
      (node (ref "C15") (pin "1") (pinfunction "1_1") (pintype "passive"))
      (node (ref "C16") (pin "1") (pinfunction "1_1") (pintype "passive"))
      (node (ref "C17") (pin "2") (pinfunction "2_2") (pintype "passive"))
      (node (ref "C18") (pin "1") (pinfunction "1_1") (pintype "passive"))
      (node (ref "C19") (pin "2") (pinfunction "2_2") (pintype "passive"))
      (node (ref "C2") (pin "1") (pinfunction "1_1") (pintype "passive"))
      (node (ref "C20") (pin "2") (pinfunction "2_2") (pintype "passive"))
      (node (ref "C21") (pin "2") (pinfunction "2_2") (pintype "passive"))
      (node (ref "C22") (pin "1") (pinfunction "1_1") (pintype "passive"))
      (node (ref "C23") (pin "2") (pinfunction "2_2") (pintype "passive"))
      (node (ref "C32") (pin "1") (pinfunction "1_1") (pintype "passive"))
      (node (ref "C33") (pin "1") (pinfunction "1_1") (pintype "passive"))
      (node (ref "C34") (pin "2") (pinfunction "2_2") (pintype "passive"))
      (node (ref "C35") (pin "2") (pinfunction "2_2") (pintype "passive"))
      (node (ref "C59") (pin "2") (pinfunction "2_2") (pintype "passive"))
      (node (ref "C60") (pin "2") (pinfunction "2_2") (pintype "passive"))
      (node (ref "C8") (pin "1") (pinfunction "1_1") (pintype "passive"))
      (node (ref "C9") (pin "2") (pinfunction "2_2") (pintype "passive"))
      (node (ref "P1") (pin "0") (pinfunction "GND_0") (pintype "power_in"))
      (node (ref "P1") (pin "4") (pinfunction "GND_4") (pintype "power_in"))
      (node (ref "P10") (pin "1") (pinfunction "1_1") (pintype "passive"))
      (node (ref "P10") (pin "10") (pinfunction "10_10") (pintype "passive"))
      (node (ref "P10") (pin "11") (pinfunction "11_11") (pintype "passive"))
      (node (ref "P10") (pin "13") (pinfunction "13_13") (pintype "passive"))
      (node (ref "P10") (pin "15") (pinfunction "15_15") (pintype "passive"))
      (node (ref "P10") (pin "3") (pinfunction "3_3") (pintype "passive"))
      (node (ref "P10") (pin "5") (pinfunction "5_5") (pintype "passive"))
      (node (ref "P10") (pin "7") (pinfunction "7_7") (pintype "passive"))
      (node (ref "P10") (pin "8") (pinfunction "8_8") (pintype "passive"))
      (node (ref "P10") (pin "9") (pinfunction "9_9") (pintype "passive"))
      (node (ref "P12") (pin "5") (pinfunction "5_5") (pintype "passive"))
      (node (ref "P12") (pin "6") (pinfunction "6_6") (pintype "passive"))
      (node (ref "P2") (pin "2") (pinfunction "2_2") (pintype "passive"))
      (node (ref "P2") (pin "4") (pinfunction "4_4") (pintype "passive"))
      (node (ref "P2") (pin "6") (pinfunction "6_6") (pintype "passive"))
      (node (ref "P4") (pin "0") (pinfunction "GND_0") (pintype "power_in"))
      (node (ref "P4") (pin "4") (pinfunction "GND_4") (pintype "power_in"))
      (node (ref "P5") (pin "A1") (pinfunction "GND_A1") (pintype "bidirectional"))
      (node (ref "P5") (pin "B1") (pinfunction "GND_B1") (pintype "bidirectional"))
      (node (ref "P6") (pin "25") (pinfunction "25_25") (pintype "passive"))
      (node (ref "P6") (pin "26") (pinfunction "26_26") (pintype "passive"))
      (node (ref "P6") (pin "27") (pinfunction "27_27") (pintype "passive"))
      (node (ref "P6") (pin "28") (pinfunction "28_28") (pintype "passive"))
      (node (ref "P6") (pin "5") (pinfunction "5_5") (pintype "passive"))
      (node (ref "P7") (pin "6") (pinfunction "6_6") (pintype "passive"))
      (node (ref "P8") (pin "1") (pinfunction "1_1") (pintype "passive"))
      (node (ref "P8") (pin "2") (pinfunction "2_2") (pintype "passive"))
      (node (ref "P8") (pin "39") (pinfunction "39_39") (pintype "passive"))
      (node (ref "P8") (pin "40") (pinfunction "40_40") (pintype "passive"))
      (node (ref "P8") (pin "41") (pinfunction "41_41") (pintype "passive"))
      (node (ref "P8") (pin "42") (pinfunction "42_42") (pintype "passive"))
      (node (ref "P9") (pin "5") (pinfunction "5_5") (pintype "passive"))
      (node (ref "P9") (pin "6") (pinfunction "6_6") (pintype "passive"))
      (node (ref "R12") (pin "2") (pinfunction "2_2") (pintype "passive"))
      (node (ref "R13") (pin "2") (pinfunction "2_2") (pintype "passive"))
      (node (ref "R16") (pin "1") (pinfunction "1_1") (pintype "passive"))
      (node (ref "R19") (pin "2") (pinfunction "2_2") (pintype "passive"))
      (node (ref "R21") (pin "2") (pinfunction "2_2") (pintype "passive"))
      (node (ref "R31") (pin "1") (pintype "passive"))
      (node (ref "R4") (pin "1") (pintype "passive"))
      (node (ref "R5") (pin "1") (pintype "passive"))
      (node (ref "S2") (pin "1") (pinfunction "1_1") (pintype "passive"))
      (node (ref "U1") (pin "0") (pinfunction "GND_0") (pintype "power_in"))
      (node (ref "U1") (pin "5") (pinfunction "AGND_5") (pintype "power_in"))
      (node (ref "U2") (pin "10") (pinfunction "VSS_5_10") (pintype "power_in"))
      (node (ref "U2") (pin "19") (pinfunction "VSSA_19") (pintype "power_in"))
      (node (ref "U2") (pin "27") (pinfunction "VSS_4_27") (pintype "power_in"))
      (node (ref "U2") (pin "49") (pinfunction "VSS_1_49") (pintype "power_in"))
      (node (ref "U2") (pin "74") (pinfunction "VSS_2_74") (pintype "power_in"))
      (node (ref "U2") (pin "99") (pinfunction "VSS_3_99") (pintype "power_in"))
      (node (ref "U4") (pin "1") (pinfunction "GND_1") (pintype "passive"))
      (node (ref "U5") (pin "1") (pinfunction "GND_1") (pintype "power_in"))
      (node (ref "U6") (pin "1") (pinfunction "GND_1") (pintype "power_in"))
    )
    (net (code "101") (name "Net-(C3-Pad2)") (class "Default")
      (node (ref "C3") (pin "2") (pinfunction "2_2") (pintype "passive"))
      (node (ref "L1") (pin "1") (pinfunction "1_1") (pintype "passive"))
      (node (ref "U1") (pin "7") (pinfunction "SW_7") (pintype "output"))
      (node (ref "U1") (pin "8") (pinfunction "SW_8") (pintype "output"))
    )
    (net (code "102") (name "Net-(D1-K)") (class "Default")
      (node (ref "D1") (pin "2") (pinfunction "K_2") (pintype "passive"))
      (node (ref "R31") (pin "2") (pintype "passive"))
    )
    (net (code "103") (name "Net-(D2-A)") (class "Default")
      (node (ref "D2") (pin "1") (pinfunction "A_1") (pintype "passive"))
      (node (ref "R1") (pin "2") (pintype "passive"))
    )
    (net (code "104") (name "Net-(D3-A)") (class "Default")
      (node (ref "D3") (pin "1") (pinfunction "A_1") (pintype "passive"))
      (node (ref "R2") (pin "2") (pintype "passive"))
    )
    (net (code "105") (name "Net-(R4-Pad2)") (class "Default")
      (node (ref "R4") (pin "2") (pintype "passive"))
      (node (ref "S1") (pin "2") (pinfunction "2_2") (pintype "passive"))
    )
    (net (code "106") (name "Net-(R22-Pad2)") (class "Default")
      (node (ref "R22") (pin "2") (pinfunction "2_2") (pintype "passive"))
      (node (ref "S3") (pin "2") (pinfunction "2_2") (pintype "passive"))
    )
    (net (code "107") (name "Net-(U1-BST)") (class "Default")
      (node (ref "C3") (pin "1") (pinfunction "1_1") (pintype "passive"))
      (node (ref "U1") (pin "6") (pinfunction "BST_6") (pintype "power_in"))
    )
    (net (code "108") (name "VBUS_CC") (class "Default")
      (node (ref "C1") (pin "2") (pinfunction "2_2") (pintype "passive"))
      (node (ref "C2") (pin "2") (pinfunction "2_2") (pintype "passive"))
      (node (ref "P10") (pin "2") (pinfunction "2_2") (pintype "passive"))
      (node (ref "P12") (pin "1") (pinfunction "1_1") (pintype "passive"))
      (node (ref "P12") (pin "3") (pinfunction "3_3") (pintype "passive"))
      (node (ref "P5") (pin "A4") (pinfunction "VBUS_A4") (pintype "bidirectional"))
      (node (ref "P5") (pin "B4") (pinfunction "VBUS_B4") (pintype "bidirectional"))
      (node (ref "U1") (pin "1") (pinfunction "AVIN_1") (pintype "power_in"))
      (node (ref "U1") (pin "10") (pinfunction "VIN_10") (pintype "power_in"))
      (node (ref "U1") (pin "9") (pinfunction "VIN_9") (pintype "power_in"))
    )
    (net (code "109") (name "VBUS_FS") (class "Default")
      (node (ref "P4") (pin "1") (pinfunction "+5V_1") (pintype "power_in"))
      (node (ref "R46") (pin "2") (pintype "passive"))
      (node (ref "U6") (pin "3") (pinfunction "VI+_3") (pintype "power_in"))
    )
    (net (code "110") (name "VBUS_HS") (class "Default")
      (node (ref "P1") (pin "1") (pinfunction "+5V_1") (pintype "power_in"))
      (node (ref "R45") (pin "2") (pintype "passive"))
      (node (ref "U5") (pin "3") (pinfunction "VI+_3") (pintype "power_in"))
    )
    (net (code "111") (name "VIO") (class "Default")
      (node (ref "C20") (pin "1") (pinfunction "1_1") (pintype "passive"))
      (node (ref "C21") (pin "1") (pinfunction "1_1") (pintype "passive"))
      (node (ref "C8") (pin "2") (pinfunction "2_2") (pintype "passive"))
      (node (ref "P11") (pin "1") (pinfunction "1_1") (pintype "passive"))
      (node (ref "P6") (pin "1") (pinfunction "1_1") (pintype "passive"))
      (node (ref "P6") (pin "3") (pinfunction "3_3") (pintype "passive"))
      (node (ref "R1") (pin "1") (pintype "passive"))
      (node (ref "R18") (pin "1") (pinfunction "1_1") (pintype "passive"))
      (node (ref "R2") (pin "1") (pintype "passive"))
      (node (ref "S3") (pin "1") (pinfunction "1_1") (pintype "passive"))
      (node (ref "U2") (pin "100") (pinfunction "VIO_3_100") (pintype "power_in"))
      (node (ref "U2") (pin "50") (pinfunction "VIO_1_50") (pintype "power_in"))
    )
    (net (code "112") (name "unconnected-(P5-D+-PadA6)") (class "Default")
      (node (ref "P5") (pin "A6") (pinfunction "D+_A6") (pintype "bidirectional+no_connect"))
    )
    (net (code "113") (name "unconnected-(P5-D+-PadB6)") (class "Default")
      (node (ref "P5") (pin "B6") (pinfunction "D+_B6") (pintype "bidirectional+no_connect"))
    )
    (net (code "114") (name "unconnected-(P5-D--PadA7)") (class "Default")
      (node (ref "P5") (pin "A7") (pinfunction "D-_A7") (pintype "bidirectional+no_connect"))
    )
    (net (code "115") (name "unconnected-(P5-D--PadB7)") (class "Default")
      (node (ref "P5") (pin "B7") (pinfunction "D-_B7") (pintype "bidirectional+no_connect"))
    )
    (net (code "116") (name "unconnected-(P5-RFU1-PadA8)") (class "Default")
      (node (ref "P5") (pin "A8") (pinfunction "RFU1_A8") (pintype "bidirectional+no_connect"))
    )
    (net (code "117") (name "unconnected-(P5-RFU1-PadB8)") (class "Default")
      (node (ref "P5") (pin "B8") (pinfunction "RFU1_B8") (pintype "bidirectional+no_connect"))
    )
    (net (code "118") (name "unconnected-(U1-NC.-Pad2)") (class "Default")
      (node (ref "U1") (pin "2") (pinfunction "NC._2") (pintype "passive"))
    )
    (net (code "119") (name "unconnected-(U1-NC.-Pad3)") (class "Default")
      (node (ref "U1") (pin "3") (pinfunction "NC._3") (pintype "passive"))
    )
  )
)
